# High_Pass_Filter.net
KiCad netlist of a schematic drawn in Altium Designer
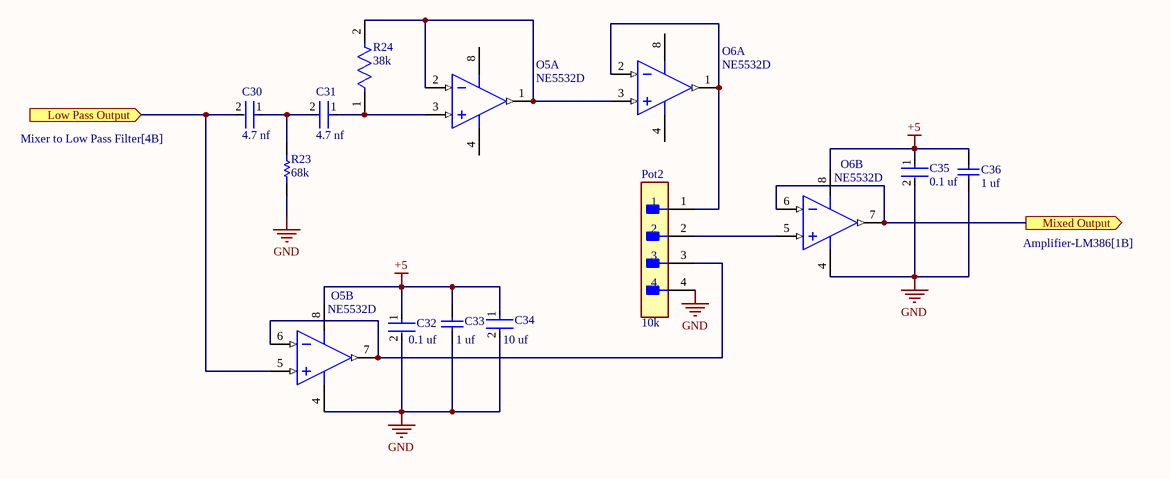
[diagram p0: High Pass Filter.SchDoc]

(export (version "E")
  (design (tool "Eeschema 10.0.6"))
  (components
    (comp (ref "C30")
      (value "4.7 nf")
      (footprint "FP-RCEWM1-MFG")
      (description "CAP CER 22UF 25V X7R RADIAL")
      (fields (field (name "TOLERANCE") "20%"))
      (libsource (lib "Altium Content Vault") (part "02cd4be3c70576c341d710602a673aa"))
    )
    (comp (ref "C31")
      (value "4.7 nf")
      (footprint "FP-RCEWM1-MFG")
      (description "CAP CER 22UF 25V X7R RADIAL")
      (fields (field (name "TOLERANCE") "20%"))
      (libsource (lib "Altium Content Vault") (part "02cd4be3c70576c341d710602a673aa"))
    )
    (comp (ref "C32")
      (value "0.1 uf")
      (footprint "FP-CL21-IPC_A")
      (description "CL21 Series 0805 1uF 16V ±10% Tolerance X7R Multilayer Ceramic Chip Capacitor")
      (fields (field (name "TOLERANCE") "10%") (field (name "VOLTAGE") "16V"))
      (libsource (lib "Altium Content Vault") (part "b4654b650e69147ec39a6b967a45e02"))
    )
    (comp (ref "C33")
      (value "1 uf")
      (footprint "CAPC2013X145X50LL20T25")
      (fields (field (name "MANUFACTURER") "Kemet") (field (name "PART NUMBER") "C0805C105K4PACTU"))
      (libsource (lib "Altium Content Vault") (part "CAP"))
    )
    (comp (ref "C34")
      (value "10 uf")
      (footprint "FP-C0805C-DG-MFG")
      (description "CAP CER 10UF 10V X5R 0805")
      (fields (field (name "TOLERANCE") "10%") (field (name "MANUFACTURER PART NUMBER") "C0805C106K8PACTU"))
      (libsource (lib "Altium Content Vault") (part "11868f565c42a9108669ba33697ecf6"))
    )
    (comp (ref "C35")
      (value "0.1 uf")
      (footprint "FP-CL21-IPC_A")
      (description "CL21 Series 0805 1uF 16V ±10% Tolerance X7R Multilayer Ceramic Chip Capacitor")
      (fields (field (name "TOLERANCE") "10%") (field (name "VOLTAGE") "16V"))
      (libsource (lib "Altium Content Vault") (part "b4654b650e69147ec39a6b967a45e02"))
    )
    (comp (ref "C36")
      (value "1 uf")
      (footprint "CAPC2013X145X50LL20T25")
      (fields (field (name "MANUFACTURER") "Kemet") (field (name "PART NUMBER") "C0805C105K4PACTU"))
      (libsource (lib "Altium Content Vault") (part "CAP"))
    )
    (comp (ref "O5")
      (value "NE5532D")
      (footprint "D0008A_L")
      (fields (field (name "MANUFACTURER") "Texas Instruments"))
      (libsource (lib "Altium Content Vault") (part "TI-AMP-D6-2-8_D"))
    )
    (comp (ref "O6")
      (value "NE5532D")
      (footprint "D0008A_L")
      (fields (field (name "MANUFACTURER") "Texas Instruments"))
      (libsource (lib "Altium Content Vault") (part "TI-AMP-D6-2-8_D"))
    )
    (comp (ref "Pot2")
      (value "10k")
      (footprint "FP-B4B-XH-A_LF_SN-MFG")
      (description "CONN HEADER VERT 4POS 2.5MM")
      (libsource (lib "Altium Content Vault") (part "299a8cea1bdcbc3624fe62c390fa72c"))
    )
    (comp (ref "R23")
      (value "68k")
      (footprint "RESC2013X70X40LL20T20")
      (fields (field (name "MANUFACTURER") "Panasonic") (field (name "PART NUMBER") "ERJ-6GEYJ683V"))
      (libsource (lib "Altium Content Vault") (part "RES"))
    )
    (comp (ref "R24")
      (value "38k")
      (footprint "FP-ERJ6EN-MFG")
      (description "RES SMD 20K OHM 1% 1/8W 0805")
      (fields (field (name "TOLERANCE") "1%"))
      (libsource (lib "Altium Content Vault") (part "1029c3af85768c4190bb7ad29bc67b5"))
    )
  )
  (nets
    (net (code "1") (name "+5") (class "Default")
      (node (ref "C32") (pin "1") (pinfunction "1_1") (pintype "passive"))
      (node (ref "C33") (pin "1") (pinfunction "1_1") (pintype "passive"))
      (node (ref "C34") (pin "1") (pinfunction "1_1") (pintype "passive"))
      (node (ref "C35") (pin "1") (pinfunction "1_1") (pintype "passive"))
      (node (ref "C36") (pin "1") (pinfunction "1_1") (pintype "passive"))
      (node (ref "O5") (pin "8") (pinfunction "VCC+_8") (pintype "power_in"))
      (node (ref "O6") (pin "8") (pinfunction "VCC+_8") (pintype "power_in"))
    )
    (net (code "2") (name "/Low Pass Output") (class "Default")
      (node (ref "C30") (pin "2") (pinfunction "2_2") (pintype "passive"))
      (node (ref "O5") (pin "5") (pinfunction "IN2+_5") (pintype "input"))
    )
    (net (code "3") (name "/Mixed Output") (class "Default")
      (node (ref "O6") (pin "6") (pinfunction "IN2-_6") (pintype "input"))
      (node (ref "O6") (pin "7") (pinfunction "OUT2_7") (pintype "output"))
    )
    (net (code "4") (name "GND") (class "Default")
      (node (ref "C32") (pin "2") (pinfunction "2_2") (pintype "passive"))
      (node (ref "C33") (pin "2") (pinfunction "2_2") (pintype "passive"))
      (node (ref "C34") (pin "2") (pinfunction "2_2") (pintype "passive"))
      (node (ref "C35") (pin "2") (pinfunction "2_2") (pintype "passive"))
      (node (ref "C36") (pin "2") (pinfunction "2_2") (pintype "passive"))
      (node (ref "O5") (pin "4") (pinfunction "VCC-_4") (pintype "power_in"))
      (node (ref "O6") (pin "4") (pinfunction "VCC-_4") (pintype "power_in"))
      (node (ref "Pot2") (pin "4") (pinfunction "4_4") (pintype "passive"))
      (node (ref "R23") (pin "2") (pinfunction "2_2") (pintype "passive"))
    )
    (net (code "5") (name "Net-(C30-Pad1)") (class "Default")
      (node (ref "C30") (pin "1") (pinfunction "1_1") (pintype "passive"))
      (node (ref "C31") (pin "2") (pinfunction "2_2") (pintype "passive"))
      (node (ref "R23") (pin "1") (pinfunction "1_1") (pintype "passive"))
    )
    (net (code "6") (name "Net-(O5A-IN1+)") (class "Default")
      (node (ref "C31") (pin "1") (pinfunction "1_1") (pintype "passive"))
      (node (ref "O5") (pin "3") (pinfunction "IN1+_3") (pintype "input"))
      (node (ref "R24") (pin "1") (pinfunction "1_1") (pintype "passive"))
    )
    (net (code "7") (name "Net-(O5A-IN1-)") (class "Default")
      (node (ref "O5") (pin "1") (pinfunction "OUT1_1") (pintype "output"))
      (node (ref "O5") (pin "2") (pinfunction "IN1-_2") (pintype "input"))
      (node (ref "O6") (pin "3") (pinfunction "IN1+_3") (pintype "input"))
      (node (ref "R24") (pin "2") (pinfunction "2_2") (pintype "passive"))
    )
    (net (code "8") (name "Net-(O5B-IN2-)") (class "Default")
      (node (ref "O5") (pin "6") (pinfunction "IN2-_6") (pintype "input"))
      (node (ref "O5") (pin "7") (pinfunction "OUT2_7") (pintype "output"))
      (node (ref "Pot2") (pin "3") (pinfunction "3_3") (pintype "passive"))
    )
    (net (code "9") (name "Net-(O6A-IN1-)") (class "Default")
      (node (ref "O6") (pin "1") (pinfunction "OUT1_1") (pintype "output"))
      (node (ref "O6") (pin "2") (pinfunction "IN1-_2") (pintype "input"))
      (node (ref "Pot2") (pin "1") (pinfunction "1_1") (pintype "passive"))
    )
    (net (code "10") (name "Net-(O6B-IN2+)") (class "Default")
      (node (ref "O6") (pin "5") (pinfunction "IN2+_5") (pintype "input"))
      (node (ref "Pot2") (pin "2") (pinfunction "2_2") (pintype "passive"))
    )
    (net (code "11") (name "unconnected-(O5A-VCC+-Pad8)") (class "Default")
      (node (ref "O5") (pin "8") (pinfunction "VCC+_8") (pintype "power_in"))
    )
    (net (code "12") (name "unconnected-(O5A-VCC--Pad4)") (class "Default")
      (node (ref "O5") (pin "4") (pinfunction "VCC-_4") (pintype "power_in"))
    )
    (net (code "13") (name "unconnected-(O6A-VCC+-Pad8)") (class "Default")
      (node (ref "O6") (pin "8") (pinfunction "VCC+_8") (pintype "power_in"))
    )
    (net (code "14") (name "unconnected-(O6A-VCC--Pad4)") (class "Default")
      (node (ref "O6") (pin "4") (pinfunction "VCC-_4") (pintype "power_in"))
    )
  )
)
